# SIGNAL1.net
KiCad netlist of a schematic drawn in Altium Designer
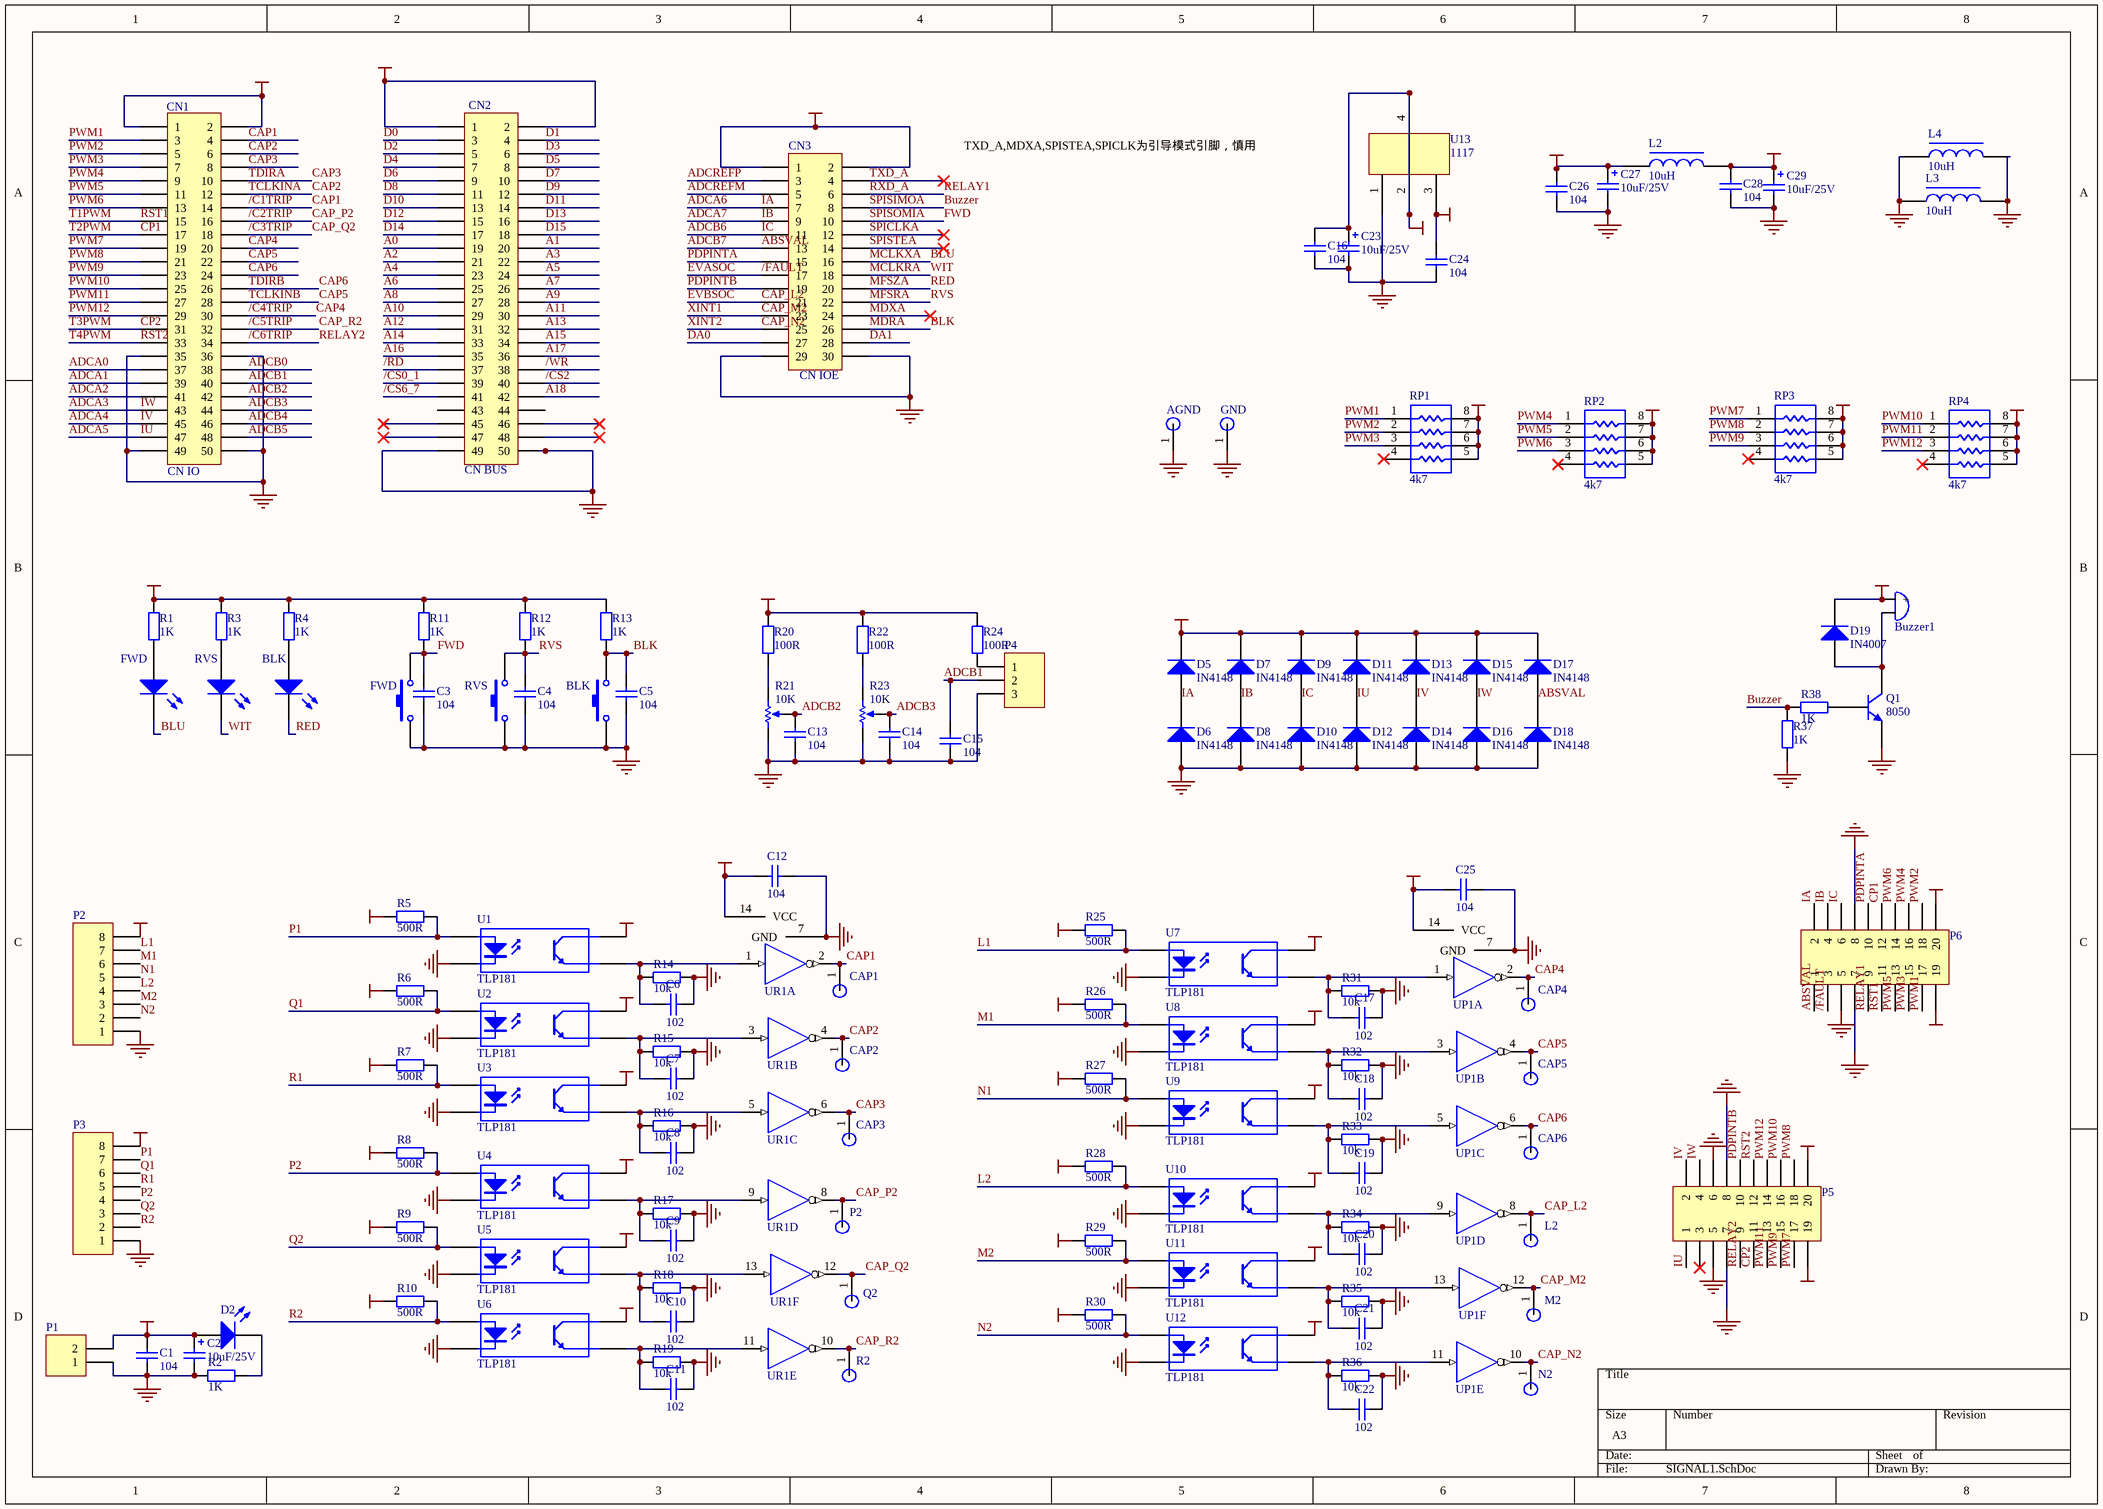
[diagram p0: SIGNAL1.SchDoc]

(export (version "E")
  (design (tool "Eeschema 10.0.6"))
  (components
    (comp (ref "Buzzer1")
      (value "BUZZER")
      (footprint "Buzzer")
      (description "蜂鸣器")
      (libsource (lib "Mylib") (part "BUZZER"))
    )
    (comp (ref "C1")
      (value "104")
      (footprint "C2012-0805")
      (description "普通电容")
      (libsource (lib "*") (part "Cap"))
    )
    (comp (ref "C2")
      (value "10uF/25V")
      (footprint "C_10UF/25V")
      (description "钽电解")
      (libsource (lib "Mylib") (part "Cap tan"))
    )
    (comp (ref "C3")
      (value "104")
      (footprint "C2012-0805")
      (description "普通电容")
      (libsource (lib "Mylib") (part "Cap"))
    )
    (comp (ref "C4")
      (value "104")
      (footprint "C2012-0805")
      (description "普通电容")
      (libsource (lib "Mylib") (part "Cap"))
    )
    (comp (ref "C5")
      (value "104")
      (footprint "C2012-0805")
      (description "普通电容")
      (libsource (lib "Mylib") (part "Cap"))
    )
    (comp (ref "C6")
      (value "102")
      (footprint "C2012-0805")
      (description "普通电容")
      (libsource (lib "*") (part "Cap"))
    )
    (comp (ref "C7")
      (value "102")
      (footprint "C2012-0805")
      (description "普通电容")
      (libsource (lib "*") (part "Cap"))
    )
    (comp (ref "C8")
      (value "102")
      (footprint "C2012-0805")
      (description "普通电容")
      (libsource (lib "*") (part "Cap"))
    )
    (comp (ref "C9")
      (value "102")
      (footprint "C2012-0805")
      (description "普通电容")
      (libsource (lib "*") (part "Cap"))
    )
    (comp (ref "C10")
      (value "102")
      (footprint "C2012-0805")
      (description "普通电容")
      (libsource (lib "*") (part "Cap"))
    )
    (comp (ref "C11")
      (value "102")
      (footprint "C2012-0805")
      (description "普通电容")
      (libsource (lib "*") (part "Cap"))
    )
    (comp (ref "C12")
      (value "104")
      (footprint "C2012-0805")
      (description "普通电容")
      (libsource (lib "*") (part "Cap"))
    )
    (comp (ref "C13")
      (value "104")
      (footprint "C2012-0805")
      (description "普通电容")
      (libsource (lib "Mylib") (part "Cap"))
    )
    (comp (ref "C14")
      (value "104")
      (footprint "C2012-0805")
      (description "普通电容")
      (libsource (lib "Mylib") (part "Cap"))
    )
    (comp (ref "C15")
      (value "104")
      (footprint "C2012-0805")
      (description "普通电容")
      (libsource (lib "Mylib") (part "Cap"))
    )
    (comp (ref "C16")
      (value "104")
      (footprint "C2012-0805")
      (description "普通电容")
      (libsource (lib "*") (part "Cap"))
    )
    (comp (ref "C17")
      (value "102")
      (footprint "C2012-0805")
      (description "普通电容")
      (libsource (lib "*") (part "Cap"))
    )
    (comp (ref "C18")
      (value "102")
      (footprint "C2012-0805")
      (description "普通电容")
      (libsource (lib "*") (part "Cap"))
    )
    (comp (ref "C19")
      (value "102")
      (footprint "C2012-0805")
      (description "普通电容")
      (libsource (lib "*") (part "Cap"))
    )
    (comp (ref "C20")
      (value "102")
      (footprint "C2012-0805")
      (description "普通电容")
      (libsource (lib "*") (part "Cap"))
    )
    (comp (ref "C21")
      (value "102")
      (footprint "C2012-0805")
      (description "普通电容")
      (libsource (lib "*") (part "Cap"))
    )
    (comp (ref "C22")
      (value "102")
      (footprint "C2012-0805")
      (description "普通电容")
      (libsource (lib "*") (part "Cap"))
    )
    (comp (ref "C23")
      (value "10uF/25V")
      (footprint "C_10UF/25V")
      (description "钽电解")
      (libsource (lib "Mylib") (part "Cap tan"))
    )
    (comp (ref "C24")
      (value "104")
      (footprint "C2012-0805")
      (description "普通电容")
      (libsource (lib "*") (part "Cap"))
    )
    (comp (ref "C25")
      (value "104")
      (footprint "C2012-0805")
      (description "普通电容")
      (libsource (lib "*") (part "Cap"))
    )
    (comp (ref "C26")
      (value "104")
      (footprint "C2012-0805")
      (description "普通电容")
      (libsource (lib "*") (part "Cap"))
    )
    (comp (ref "C27")
      (value "10uF/25V")
      (footprint "C_10UF/25V")
      (description "钽电解")
      (libsource (lib "Mylib") (part "Cap tan"))
    )
    (comp (ref "C28")
      (value "104")
      (footprint "C2012-0805")
      (description "普通电容")
      (libsource (lib "*") (part "Cap"))
    )
    (comp (ref "C29")
      (value "10uF/25V")
      (footprint "C_10UF/25V")
      (description "钽电解")
      (libsource (lib "Mylib") (part "Cap tan"))
    )
    (comp (ref "CN1")
      (value "CN IO")
      (footprint "HDR2X25")
      (description "Header, 25-Pin, Dual row")
      (fields (field (name "PUBLISHER") "Altium Limited"))
      (libsource (lib "Miscellaneous Connectors") (part "Header 25X2"))
    )
    (comp (ref "CN2")
      (value "CN BUS")
      (footprint "HDR2X25")
      (description "Header, 25-Pin, Dual row")
      (fields (field (name "PUBLISHER") "Altium Limited"))
      (libsource (lib "Miscellaneous Connectors") (part "Header 25X2"))
    )
    (comp (ref "CN3")
      (value "CN IOE")
      (footprint "HDR2X15")
      (description "Header, 15-Pin, Dual row")
      (fields (field (name "PUBLISHER") "Altium Limited"))
      (libsource (lib "Miscellaneous Connectors") (part "Header 15X2"))
    )
    (comp (ref "D1") (value "FWD") (footprint "LED-SMD") (libsource (lib "*") (part "LED")))
    (comp (ref "D2") (value "~") (footprint "LED-SMD") (libsource (lib "Mylib") (part "LED")))
    (comp (ref "D3") (value "RVS") (footprint "LED-SMD") (libsource (lib "*") (part "LED")))
    (comp (ref "D4") (value "BLK") (footprint "LED-SMD") (libsource (lib "*") (part "LED")))
    (comp (ref "D5")
      (value "IN4148")
      (footprint "IN4148")
      (description "开关二极管")
      (libsource (lib "Mylib") (part "Diode IN4148"))
    )
    (comp (ref "D6")
      (value "IN4148")
      (footprint "IN4148")
      (description "开关二极管")
      (libsource (lib "Mylib") (part "Diode IN4148"))
    )
    (comp (ref "D7")
      (value "IN4148")
      (footprint "IN4148")
      (description "开关二极管")
      (libsource (lib "Mylib") (part "Diode IN4148"))
    )
    (comp (ref "D8")
      (value "IN4148")
      (footprint "IN4148")
      (description "开关二极管")
      (libsource (lib "Mylib") (part "Diode IN4148"))
    )
    (comp (ref "D9")
      (value "IN4148")
      (footprint "IN4148")
      (description "开关二极管")
      (libsource (lib "Mylib") (part "Diode IN4148"))
    )
    (comp (ref "D10")
      (value "IN4148")
      (footprint "IN4148")
      (description "开关二极管")
      (libsource (lib "Mylib") (part "Diode IN4148"))
    )
    (comp (ref "D11")
      (value "IN4148")
      (footprint "IN4148")
      (description "开关二极管")
      (libsource (lib "Mylib") (part "Diode IN4148"))
    )
    (comp (ref "D12")
      (value "IN4148")
      (footprint "IN4148")
      (description "开关二极管")
      (libsource (lib "Mylib") (part "Diode IN4148"))
    )
    (comp (ref "D13")
      (value "IN4148")
      (footprint "IN4148")
      (description "开关二极管")
      (libsource (lib "Mylib") (part "Diode IN4148"))
    )
    (comp (ref "D14")
      (value "IN4148")
      (footprint "IN4148")
      (description "开关二极管")
      (libsource (lib "Mylib") (part "Diode IN4148"))
    )
    (comp (ref "D15")
      (value "IN4148")
      (footprint "IN4148")
      (description "开关二极管")
      (libsource (lib "Mylib") (part "Diode IN4148"))
    )
    (comp (ref "D16")
      (value "IN4148")
      (footprint "IN4148")
      (description "开关二极管")
      (libsource (lib "Mylib") (part "Diode IN4148"))
    )
    (comp (ref "D17")
      (value "IN4148")
      (footprint "IN4148")
      (description "开关二极管")
      (libsource (lib "Mylib") (part "Diode IN4148"))
    )
    (comp (ref "D18")
      (value "IN4148")
      (footprint "IN4148")
      (description "开关二极管")
      (libsource (lib "Mylib") (part "Diode IN4148"))
    )
    (comp (ref "D19")
      (value "IN4007")
      (footprint "DIODE4007")
      (description "普通整流二极管")
      (libsource (lib "Mylib") (part "Diode IN4007"))
    )
    (comp (ref "key1")
      (value "FWD")
      (footprint "KEY1")
      (description "按键")
      (libsource (lib "Mylib") (part "KEY"))
    )
    (comp (ref "key2")
      (value "RVS")
      (footprint "KEY1")
      (description "按键")
      (libsource (lib "Mylib") (part "KEY"))
    )
    (comp (ref "key3")
      (value "BLK")
      (footprint "KEY1")
      (description "按键")
      (libsource (lib "Mylib") (part "KEY"))
    )
    (comp (ref "L2") (value "10uH") (footprint "R2012-0805") (libsource (lib "*") (part "Inductor")))
    (comp (ref "L3") (value "10uH") (footprint "R2012-0805") (libsource (lib "*") (part "Inductor")))
    (comp (ref "L4") (value "10uH") (footprint "R2012-0805") (libsource (lib "*") (part "Inductor")))
    (comp (ref "P1")
      (value "Header 2")
      (footprint "HDR1X2")
      (description "Header, 2-Pin")
      (fields (field (name "PUBLISHER") "Altium Limited"))
      (libsource (lib "Miscellaneous Connectors") (part "Header 2"))
    )
    (comp (ref "P2")
      (value "Header 8")
      (footprint "HDR1X8")
      (description "Header, 8-Pin")
      (fields (field (name "PUBLISHER") "Altium Limited"))
      (libsource (lib "Miscellaneous Connectors") (part "Header 8"))
    )
    (comp (ref "P3")
      (value "Header 8")
      (footprint "HDR1X8")
      (description "Header, 8-Pin")
      (fields (field (name "PUBLISHER") "Altium Limited"))
      (libsource (lib "Miscellaneous Connectors") (part "Header 8"))
    )
    (comp (ref "P4")
      (value "Header 3")
      (footprint "HDR1X3")
      (description "Header, 3-Pin")
      (fields (field (name "PUBLISHER") "Altium Limited"))
      (libsource (lib "Miscellaneous Connectors") (part "Header 3"))
    )
    (comp (ref "P5")
      (value "Header 10X2")
      (footprint "HDR2X10")
      (description "Header, 10-Pin, Dual row")
      (fields (field (name "PUBLISHER") "Altium Limited"))
      (libsource (lib "Miscellaneous Connectors") (part "Header 10X2"))
    )
    (comp (ref "P6")
      (value "Header 10X2")
      (footprint "HDR2X10")
      (description "Header, 10-Pin, Dual row")
      (fields (field (name "PUBLISHER") "Altium Limited"))
      (libsource (lib "Miscellaneous Connectors") (part "Header 10X2"))
    )
    (comp (ref "Q1") (value "8050") (footprint "NPN8050") (libsource (lib "Mylib") (part "NPN8050")))
    (comp (ref "R1") (value "1K") (footprint "R2012-0805") (libsource (lib "") (part "Res_2")))
    (comp (ref "R2") (value "1K") (footprint "R2012-0805") (libsource (lib "*") (part "Res")))
    (comp (ref "R3") (value "1K") (footprint "R2012-0805") (libsource (lib "") (part "Res_2")))
    (comp (ref "R4") (value "1K") (footprint "R2012-0805") (libsource (lib "") (part "Res_2")))
    (comp (ref "R5") (value "500R") (footprint "R2012-0805") (libsource (lib "Mylib") (part "Res")))
    (comp (ref "R6") (value "500R") (footprint "R2012-0805") (libsource (lib "Mylib") (part "Res")))
    (comp (ref "R7") (value "500R") (footprint "R2012-0805") (libsource (lib "Mylib") (part "Res")))
    (comp (ref "R8") (value "500R") (footprint "R2012-0805") (libsource (lib "Mylib") (part "Res")))
    (comp (ref "R9") (value "500R") (footprint "R2012-0805") (libsource (lib "Mylib") (part "Res")))
    (comp (ref "R10") (value "500R") (footprint "R2012-0805") (libsource (lib "Mylib") (part "Res")))
    (comp (ref "R11") (value "1K") (footprint "R2012-0805") (libsource (lib "") (part "Res_2")))
    (comp (ref "R12") (value "1K") (footprint "R2012-0805") (libsource (lib "") (part "Res_2")))
    (comp (ref "R13") (value "1K") (footprint "R2012-0805") (libsource (lib "") (part "Res_2")))
    (comp (ref "R14") (value "10k") (footprint "R2012-0805") (libsource (lib "Mylib") (part "Res")))
    (comp (ref "R15") (value "10k") (footprint "R2012-0805") (libsource (lib "Mylib") (part "Res")))
    (comp (ref "R16") (value "10k") (footprint "R2012-0805") (libsource (lib "Mylib") (part "Res")))
    (comp (ref "R17") (value "10k") (footprint "R2012-0805") (libsource (lib "Mylib") (part "Res")))
    (comp (ref "R18") (value "10k") (footprint "R2012-0805") (libsource (lib "Mylib") (part "Res")))
    (comp (ref "R19") (value "10k") (footprint "R2012-0805") (libsource (lib "Mylib") (part "Res")))
    (comp (ref "R20") (value "100R") (footprint "R2012-0805") (libsource (lib "") (part "Res_2")))
    (comp (ref "R21")
      (value "10K")
      (footprint "Res3296")
      (description "微调电位器")
      (libsource (lib "Mylib") (part "Res3296"))
    )
    (comp (ref "R22") (value "100R") (footprint "R2012-0805") (libsource (lib "") (part "Res_2")))
    (comp (ref "R23")
      (value "10K")
      (footprint "Res3296")
      (description "微调电位器")
      (libsource (lib "Mylib") (part "Res3296"))
    )
    (comp (ref "R24") (value "100R") (footprint "R2012-0805") (libsource (lib "") (part "Res_2")))
    (comp (ref "R25") (value "500R") (footprint "R2012-0805") (libsource (lib "Mylib") (part "Res")))
    (comp (ref "R26") (value "500R") (footprint "R2012-0805") (libsource (lib "Mylib") (part "Res")))
    (comp (ref "R27") (value "500R") (footprint "R2012-0805") (libsource (lib "Mylib") (part "Res")))
    (comp (ref "R28") (value "500R") (footprint "R2012-0805") (libsource (lib "Mylib") (part "Res")))
    (comp (ref "R29") (value "500R") (footprint "R2012-0805") (libsource (lib "Mylib") (part "Res")))
    (comp (ref "R30") (value "500R") (footprint "R2012-0805") (libsource (lib "Mylib") (part "Res")))
    (comp (ref "R31") (value "10k") (footprint "R2012-0805") (libsource (lib "Mylib") (part "Res")))
    (comp (ref "R32") (value "10k") (footprint "R2012-0805") (libsource (lib "Mylib") (part "Res")))
    (comp (ref "R33") (value "10k") (footprint "R2012-0805") (libsource (lib "Mylib") (part "Res")))
    (comp (ref "R34") (value "10k") (footprint "R2012-0805") (libsource (lib "Mylib") (part "Res")))
    (comp (ref "R35") (value "10k") (footprint "R2012-0805") (libsource (lib "Mylib") (part "Res")))
    (comp (ref "R36") (value "10k") (footprint "R2012-0805") (libsource (lib "Mylib") (part "Res")))
    (comp (ref "R37") (value "1K") (footprint "R2012-0805") (libsource (lib "") (part "Res_3")))
    (comp (ref "R38") (value "1K") (footprint "R2012-0805") (libsource (lib "") (part "Res_1")))
    (comp (ref "RP1") (value "4k7") (footprint "Res_Pack4") (libsource (lib "Mylib") (part "Res_Pack4")))
    (comp (ref "RP2") (value "4k7") (footprint "Res_Pack4") (libsource (lib "Mylib") (part "Res_Pack4")))
    (comp (ref "RP3") (value "4k7") (footprint "Res_Pack4") (libsource (lib "Mylib") (part "Res_Pack4")))
    (comp (ref "RP4") (value "4k7") (footprint "Res_Pack4") (libsource (lib "Mylib") (part "Res_Pack4")))
    (comp (ref "T1")
      (value "CAP1")
      (footprint "PIN1")
      (description "测试脚")
      (libsource (lib "Mylib") (part "TP"))
    )
    (comp (ref "T2")
      (value "CAP2")
      (footprint "PIN1")
      (description "测试脚")
      (libsource (lib "Mylib") (part "TP"))
    )
    (comp (ref "T3")
      (value "P2")
      (footprint "PIN1")
      (description "测试脚")
      (libsource (lib "Mylib") (part "TP"))
    )
    (comp (ref "T4")
      (value "CAP3")
      (footprint "PIN1")
      (description "测试脚")
      (libsource (lib "Mylib") (part "TP"))
    )
    (comp (ref "T5")
      (value "R2")
      (footprint "PIN1")
      (description "测试脚")
      (libsource (lib "Mylib") (part "TP"))
    )
    (comp (ref "T6")
      (value "Q2")
      (footprint "PIN1")
      (description "测试脚")
      (libsource (lib "Mylib") (part "TP"))
    )
    (comp (ref "T7")
      (value "AGND")
      (footprint "PIN1")
      (description "测试脚")
      (libsource (lib "Mylib") (part "TP"))
    )
    (comp (ref "T8")
      (value "GND")
      (footprint "PIN1")
      (description "测试脚")
      (libsource (lib "Mylib") (part "TP"))
    )
    (comp (ref "T9")
      (value "CAP4")
      (footprint "PIN1")
      (description "测试脚")
      (libsource (lib "Mylib") (part "TP"))
    )
    (comp (ref "T10")
      (value "CAP5")
      (footprint "PIN1")
      (description "测试脚")
      (libsource (lib "Mylib") (part "TP"))
    )
    (comp (ref "T11")
      (value "CAP6")
      (footprint "PIN1")
      (description "测试脚")
      (libsource (lib "Mylib") (part "TP"))
    )
    (comp (ref "T12")
      (value "L2")
      (footprint "PIN1")
      (description "测试脚")
      (libsource (lib "Mylib") (part "TP"))
    )
    (comp (ref "T13")
      (value "N2")
      (footprint "PIN1")
      (description "测试脚")
      (libsource (lib "Mylib") (part "TP"))
    )
    (comp (ref "T14")
      (value "M2")
      (footprint "PIN1")
      (description "测试脚")
      (libsource (lib "Mylib") (part "TP"))
    )
    (comp (ref "U1") (value "TLP181") (footprint "TLP181") (libsource (lib "Mylib") (part "TLP181")))
    (comp (ref "U2") (value "TLP181") (footprint "TLP181") (libsource (lib "Mylib") (part "TLP181")))
    (comp (ref "U3") (value "TLP181") (footprint "TLP181") (libsource (lib "Mylib") (part "TLP181")))
    (comp (ref "U4") (value "TLP181") (footprint "TLP181") (libsource (lib "Mylib") (part "TLP181")))
    (comp (ref "U5") (value "TLP181") (footprint "TLP181") (libsource (lib "Mylib") (part "TLP181")))
    (comp (ref "U6") (value "TLP181") (footprint "TLP181") (libsource (lib "Mylib") (part "TLP181")))
    (comp (ref "U7") (value "TLP181") (footprint "TLP181") (libsource (lib "Mylib") (part "TLP181")))
    (comp (ref "U8") (value "TLP181") (footprint "TLP181") (libsource (lib "Mylib") (part "TLP181")))
    (comp (ref "U9") (value "TLP181") (footprint "TLP181") (libsource (lib "Mylib") (part "TLP181")))
    (comp (ref "U10") (value "TLP181") (footprint "TLP181") (libsource (lib "Mylib") (part "TLP181")))
    (comp (ref "U11") (value "TLP181") (footprint "TLP181") (libsource (lib "Mylib") (part "TLP181")))
    (comp (ref "U12") (value "TLP181") (footprint "TLP181") (libsource (lib "Mylib") (part "TLP181")))
    (comp (ref "U13") (value "1117") (footprint "1117-3.3V") (libsource (lib "*") (part "1117")))
    (comp (ref "UP1")
      (value "74HC14")
      (footprint "74HC14")
      (description "六路，施密特触发反相器")
      (libsource (lib "*") (part "74HC14"))
    )
    (comp (ref "UR1")
      (value "74HC14")
      (footprint "74HC14")
      (description "六路，施密特触发反相器")
      (libsource (lib "*") (part "74HC14"))
    )
  )
  (nets
    (net (code "1") (name "+5V") (class "Default")
      (node (ref "Buzzer1") (pin "1") (pinfunction "+_1") (pintype "passive"))
      (node (ref "C26") (pin "2") (pinfunction "2_2") (pintype "passive"))
      (node (ref "C27") (pin "1") (pinfunction "1_1") (pintype "passive"))
      (node (ref "CN1") (pin "1") (pinfunction "1_1") (pintype "passive"))
      (node (ref "CN1") (pin "2") (pinfunction "2_2") (pintype "passive"))
      (node (ref "CN2") (pin "1") (pinfunction "1_1") (pintype "passive"))
      (node (ref "CN2") (pin "2") (pinfunction "2_2") (pintype "passive"))
      (node (ref "CN3") (pin "1") (pinfunction "1_1") (pintype "passive"))
      (node (ref "CN3") (pin "2") (pinfunction "2_2") (pintype "passive"))
      (node (ref "D19") (pin "2") (pinfunction "K_2") (pintype "passive"))
      (node (ref "L2") (pin "1") (pinfunction "1_1") (pintype "passive"))
      (node (ref "P5") (pin "19") (pinfunction "19_19") (pintype "passive"))
      (node (ref "P5") (pin "20") (pinfunction "20_20") (pintype "passive"))
      (node (ref "P6") (pin "19") (pinfunction "19_19") (pintype "passive"))
      (node (ref "P6") (pin "20") (pinfunction "20_20") (pintype "passive"))
    )
    (net (code "2") (name "+5V_HALL") (class "Default")
      (node (ref "C1") (pin "2") (pinfunction "2_2") (pintype "passive"))
      (node (ref "C2") (pin "1") (pinfunction "1_1") (pintype "passive"))
      (node (ref "D2") (pin "1") (pinfunction "A_1") (pintype "passive"))
      (node (ref "P1") (pin "2") (pinfunction "2_2") (pintype "passive"))
      (node (ref "P2") (pin "8") (pinfunction "8_8") (pintype "passive"))
      (node (ref "P3") (pin "8") (pinfunction "8_8") (pintype "passive"))
      (node (ref "R10") (pin "1") (pinfunction "1_1") (pintype "passive"))
      (node (ref "R25") (pin "1") (pinfunction "1_1") (pintype "passive"))
      (node (ref "R26") (pin "1") (pinfunction "1_1") (pintype "passive"))
      (node (ref "R27") (pin "1") (pinfunction "1_1") (pintype "passive"))
      (node (ref "R28") (pin "1") (pinfunction "1_1") (pintype "passive"))
      (node (ref "R29") (pin "1") (pinfunction "1_1") (pintype "passive"))
      (node (ref "R30") (pin "1") (pinfunction "1_1") (pintype "passive"))
      (node (ref "R5") (pin "1") (pinfunction "1_1") (pintype "passive"))
      (node (ref "R6") (pin "1") (pinfunction "1_1") (pintype "passive"))
      (node (ref "R7") (pin "1") (pinfunction "1_1") (pintype "passive"))
      (node (ref "R8") (pin "1") (pinfunction "1_1") (pintype "passive"))
      (node (ref "R9") (pin "1") (pinfunction "1_1") (pintype "passive"))
    )
    (net (code "3") (name "/A0") (class "Default")
      (node (ref "CN2") (pin "19") (pinfunction "19_19") (pintype "passive"))
    )
    (net (code "4") (name "/A1") (class "Default")
      (node (ref "CN2") (pin "20") (pinfunction "20_20") (pintype "passive"))
    )
    (net (code "5") (name "/A2") (class "Default")
      (node (ref "CN2") (pin "21") (pinfunction "21_21") (pintype "passive"))
    )
    (net (code "6") (name "/A3") (class "Default")
      (node (ref "CN2") (pin "22") (pinfunction "22_22") (pintype "passive"))
    )
    (net (code "7") (name "/A4") (class "Default")
      (node (ref "CN2") (pin "23") (pinfunction "23_23") (pintype "passive"))
    )
    (net (code "8") (name "/A5") (class "Default")
      (node (ref "CN2") (pin "24") (pinfunction "24_24") (pintype "passive"))
    )
    (net (code "9") (name "/A6") (class "Default")
      (node (ref "CN2") (pin "25") (pinfunction "25_25") (pintype "passive"))
    )
    (net (code "10") (name "/A7") (class "Default")
      (node (ref "CN2") (pin "26") (pinfunction "26_26") (pintype "passive"))
    )
    (net (code "11") (name "/A8") (class "Default")
      (node (ref "CN2") (pin "27") (pinfunction "27_27") (pintype "passive"))
    )
    (net (code "12") (name "/A9") (class "Default")
      (node (ref "CN2") (pin "28") (pinfunction "28_28") (pintype "passive"))
    )
    (net (code "13") (name "/A10") (class "Default")
      (node (ref "CN2") (pin "29") (pinfunction "29_29") (pintype "passive"))
    )
    (net (code "14") (name "/A11") (class "Default")
      (node (ref "CN2") (pin "30") (pinfunction "30_30") (pintype "passive"))
    )
    (net (code "15") (name "/A12") (class "Default")
      (node (ref "CN2") (pin "31") (pinfunction "31_31") (pintype "passive"))
    )
    (net (code "16") (name "/A13") (class "Default")
      (node (ref "CN2") (pin "32") (pinfunction "32_32") (pintype "passive"))
    )
    (net (code "17") (name "/A14") (class "Default")
      (node (ref "CN2") (pin "33") (pinfunction "33_33") (pintype "passive"))
    )
    (net (code "18") (name "/A15") (class "Default")
      (node (ref "CN2") (pin "34") (pinfunction "34_34") (pintype "passive"))
    )
    (net (code "19") (name "/A16") (class "Default")
      (node (ref "CN2") (pin "35") (pinfunction "35_35") (pintype "passive"))
    )
    (net (code "20") (name "/A17") (class "Default")
      (node (ref "CN2") (pin "36") (pinfunction "36_36") (pintype "passive"))
    )
    (net (code "21") (name "/A18") (class "Default")
      (node (ref "CN2") (pin "42") (pinfunction "42_42") (pintype "passive"))
    )
    (net (code "22") (name "/ABSVAL") (class "Default")
      (node (ref "CN3") (pin "13") (pinfunction "13_13") (pintype "passive"))
      (node (ref "D17") (pin "1") (pinfunction "A_1") (pintype "passive"))
      (node (ref "D18") (pin "2") (pinfunction "K_2") (pintype "passive"))
      (node (ref "P6") (pin "1") (pinfunction "1_1") (pintype "passive"))
    )
    (net (code "23") (name "/ADCA0") (class "Default")
      (node (ref "CN1") (pin "37") (pinfunction "37_37") (pintype "passive"))
    )
    (net (code "24") (name "/ADCA1") (class "Default")
      (node (ref "CN1") (pin "39") (pinfunction "39_39") (pintype "passive"))
    )
    (net (code "25") (name "/ADCA2") (class "Default")
      (node (ref "CN1") (pin "41") (pinfunction "41_41") (pintype "passive"))
    )
    (net (code "26") (name "/ADCA3") (class "Default")
      (node (ref "CN1") (pin "43") (pinfunction "43_43") (pintype "passive"))
      (node (ref "D15") (pin "1") (pinfunction "A_1") (pintype "passive"))
      (node (ref "D16") (pin "2") (pinfunction "K_2") (pintype "passive"))
      (node (ref "P5") (pin "4") (pinfunction "4_4") (pintype "passive"))
    )
    (net (code "27") (name "/ADCA4") (class "Default")
      (node (ref "CN1") (pin "45") (pinfunction "45_45") (pintype "passive"))
      (node (ref "D13") (pin "1") (pinfunction "A_1") (pintype "passive"))
      (node (ref "D14") (pin "2") (pinfunction "K_2") (pintype "passive"))
      (node (ref "P5") (pin "2") (pinfunction "2_2") (pintype "passive"))
    )
    (net (code "28") (name "/ADCA5") (class "Default")
      (node (ref "CN1") (pin "47") (pinfunction "47_47") (pintype "passive"))
      (node (ref "D11") (pin "1") (pinfunction "A_1") (pintype "passive"))
      (node (ref "D12") (pin "2") (pinfunction "K_2") (pintype "passive"))
      (node (ref "P5") (pin "1") (pinfunction "1_1") (pintype "passive"))
    )
    (net (code "29") (name "/ADCA6") (class "Default")
      (node (ref "CN3") (pin "7") (pinfunction "7_7") (pintype "passive"))
      (node (ref "D5") (pin "1") (pinfunction "A_1") (pintype "passive"))
      (node (ref "D6") (pin "2") (pinfunction "K_2") (pintype "passive"))
      (node (ref "P6") (pin "2") (pinfunction "2_2") (pintype "passive"))
    )
    (net (code "30") (name "/ADCA7") (class "Default")
      (node (ref "CN3") (pin "9") (pinfunction "9_9") (pintype "passive"))
      (node (ref "D7") (pin "1") (pinfunction "A_1") (pintype "passive"))
      (node (ref "D8") (pin "2") (pinfunction "K_2") (pintype "passive"))
      (node (ref "P6") (pin "4") (pinfunction "4_4") (pintype "passive"))
    )
    (net (code "31") (name "/ADCB0") (class "Default")
      (node (ref "CN1") (pin "38") (pinfunction "38_38") (pintype "passive"))
    )
    (net (code "32") (name "/ADCB1") (class "Default")
      (node (ref "C15") (pin "2") (pinfunction "2_2") (pintype "passive"))
      (node (ref "CN1") (pin "40") (pinfunction "40_40") (pintype "passive"))
      (node (ref "P4") (pin "2") (pinfunction "2_2") (pintype "passive"))
    )
    (net (code "33") (name "/ADCB2") (class "Default")
      (node (ref "C13") (pin "2") (pinfunction "2_2") (pintype "passive"))
      (node (ref "CN1") (pin "42") (pinfunction "42_42") (pintype "passive"))
      (node (ref "R21") (pin "2") (pinfunction "TAP_2") (pintype "passive"))
    )
    (net (code "34") (name "/ADCB3") (class "Default")
      (node (ref "C14") (pin "2") (pinfunction "2_2") (pintype "passive"))
      (node (ref "CN1") (pin "44") (pinfunction "44_44") (pintype "passive"))
      (node (ref "R23") (pin "2") (pinfunction "TAP_2") (pintype "passive"))
    )
    (net (code "35") (name "/ADCB4") (class "Default")
      (node (ref "CN1") (pin "46") (pinfunction "46_46") (pintype "passive"))
    )
    (net (code "36") (name "/ADCB5") (class "Default")
      (node (ref "CN1") (pin "48") (pinfunction "48_48") (pintype "passive"))
    )
    (net (code "37") (name "/ADCB6") (class "Default")
      (node (ref "CN3") (pin "11") (pinfunction "11_11") (pintype "passive"))
      (node (ref "D10") (pin "2") (pinfunction "K_2") (pintype "passive"))
      (node (ref "D9") (pin "1") (pinfunction "A_1") (pintype "passive"))
      (node (ref "P6") (pin "6") (pinfunction "6_6") (pintype "passive"))
    )
    (net (code "38") (name "/ADCREFM") (class "Default")
      (node (ref "CN3") (pin "5") (pinfunction "5_5") (pintype "passive"))
    )
    (net (code "39") (name "/ADCREFP") (class "Default")
      (node (ref "CN3") (pin "3") (pinfunction "3_3") (pintype "passive"))
    )
    (net (code "40") (name "/BLK") (class "Default")
      (node (ref "C5") (pin "2") (pinfunction "2_2") (pintype "passive"))
      (node (ref "CN3") (pin "26") (pinfunction "26_26") (pintype "passive"))
      (node (ref "R13") (pin "1") (pinfunction "1_1") (pintype "passive"))
      (node (ref "key3") (pin "3") (pinfunction "3_3") (pintype "passive"))
    )
    (net (code "41") (name "/BLU") (class "Default")
      (node (ref "CN3") (pin "16") (pinfunction "16_16") (pintype "passive"))
      (node (ref "D1") (pin "2") (pinfunction "K_2") (pintype "passive"))
    )
    (net (code "42") (name "/Buzzer") (class "Default")
      (node (ref "CN3") (pin "8") (pinfunction "8_8") (pintype "passive"))
      (node (ref "R37") (pin "1") (pinfunction "1_1") (pintype "passive"))
      (node (ref "R38") (pin "2") (pinfunction "2_2") (pintype "passive"))
    )
    (net (code "43") (name "/CAP1") (class "Default")
      (node (ref "CN1") (pin "14") (pinfunction "14_14") (pintype "passive"))
      (node (ref "CN1") (pin "4") (pinfunction "4_4") (pintype "passive"))
      (node (ref "T1") (pin "1") (pinfunction "A_1") (pintype "passive"))
      (node (ref "UR1") (pin "2") (pinfunction "Y_2") (pintype "output"))
    )
    (net (code "44") (name "/CAP2") (class "Default")
      (node (ref "CN1") (pin "12") (pinfunction "12_12") (pintype "passive"))
      (node (ref "CN1") (pin "6") (pinfunction "6_6") (pintype "passive"))
      (node (ref "T2") (pin "1") (pinfunction "A_1") (pintype "passive"))
      (node (ref "UR1") (pin "4") (pinfunction "Y_4") (pintype "output"))
    )
    (net (code "45") (name "/CAP3") (class "Default")
      (node (ref "CN1") (pin "10") (pinfunction "10_10") (pintype "passive"))
      (node (ref "CN1") (pin "8") (pinfunction "8_8") (pintype "passive"))
      (node (ref "T4") (pin "1") (pinfunction "A_1") (pintype "passive"))
      (node (ref "UR1") (pin "6") (pinfunction "Y_6") (pintype "output"))
    )
    (net (code "46") (name "/CAP4") (class "Default")
      (node (ref "CN1") (pin "20") (pinfunction "20_20") (pintype "passive"))
      (node (ref "CN1") (pin "30") (pinfunction "30_30") (pintype "passive"))
      (node (ref "T9") (pin "1") (pinfunction "A_1") (pintype "passive"))
      (node (ref "UP1") (pin "2") (pinfunction "Y_2") (pintype "output"))
    )
    (net (code "47") (name "/CAP5") (class "Default")
      (node (ref "CN1") (pin "22") (pinfunction "22_22") (pintype "passive"))
      (node (ref "CN1") (pin "28") (pinfunction "28_28") (pintype "passive"))
      (node (ref "T10") (pin "1") (pinfunction "A_1") (pintype "passive"))
      (node (ref "UP1") (pin "4") (pinfunction "Y_4") (pintype "output"))
    )
    (net (code "48") (name "/CAP6") (class "Default")
      (node (ref "CN1") (pin "24") (pinfunction "24_24") (pintype "passive"))
      (node (ref "CN1") (pin "26") (pinfunction "26_26") (pintype "passive"))
      (node (ref "T11") (pin "1") (pinfunction "A_1") (pintype "passive"))
      (node (ref "UP1") (pin "6") (pinfunction "Y_6") (pintype "output"))
    )
    (net (code "49") (name "/CAP_L2") (class "Default")
      (node (ref "CN3") (pin "21") (pinfunction "21_21") (pintype "passive"))
      (node (ref "T12") (pin "1") (pinfunction "A_1") (pintype "passive"))
      (node (ref "UP1") (pin "8") (pinfunction "Y_8") (pintype "output"))
    )
    (net (code "50") (name "/CAP_M2") (class "Default")
      (node (ref "CN3") (pin "23") (pinfunction "23_23") (pintype "passive"))
      (node (ref "T14") (pin "1") (pinfunction "A_1") (pintype "passive"))
      (node (ref "UP1") (pin "12") (pinfunction "Y_12") (pintype "output"))
    )
    (net (code "51") (name "/CAP_N2") (class "Default")
      (node (ref "CN3") (pin "25") (pinfunction "25_25") (pintype "passive"))
      (node (ref "T13") (pin "1") (pinfunction "A_1") (pintype "passive"))
      (node (ref "UP1") (pin "10") (pinfunction "Y_10") (pintype "output"))
    )
    (net (code "52") (name "/CAP_P2") (class "Default")
      (node (ref "CN1") (pin "16") (pinfunction "16_16") (pintype "passive"))
      (node (ref "T3") (pin "1") (pinfunction "A_1") (pintype "passive"))
      (node (ref "UR1") (pin "8") (pinfunction "Y_8") (pintype "output"))
    )
    (net (code "53") (name "/CAP_Q2") (class "Default")
      (node (ref "CN1") (pin "18") (pinfunction "18_18") (pintype "passive"))
      (node (ref "T6") (pin "1") (pinfunction "A_1") (pintype "passive"))
      (node (ref "UR1") (pin "12") (pinfunction "Y_12") (pintype "output"))
    )
    (net (code "54") (name "/CAP_R2") (class "Default")
      (node (ref "CN1") (pin "32") (pinfunction "32_32") (pintype "passive"))
      (node (ref "T5") (pin "1") (pinfunction "A_1") (pintype "passive"))
      (node (ref "UR1") (pin "10") (pinfunction "Y_10") (pintype "output"))
    )
    (net (code "55") (name "/CP1") (class "Default")
      (node (ref "CN1") (pin "17") (pinfunction "17_17") (pintype "passive"))
      (node (ref "P6") (pin "12") (pinfunction "12_12") (pintype "passive"))
    )
    (net (code "56") (name "/CP2") (class "Default")
      (node (ref "CN1") (pin "31") (pinfunction "31_31") (pintype "passive"))
      (node (ref "P5") (pin "11") (pinfunction "11_11") (pintype "passive"))
    )
    (net (code "57") (name "/D0") (class "Default")
      (node (ref "CN2") (pin "3") (pinfunction "3_3") (pintype "passive"))
    )
    (net (code "58") (name "/D1") (class "Default")
      (node (ref "CN2") (pin "4") (pinfunction "4_4") (pintype "passive"))
    )
    (net (code "59") (name "/D2") (class "Default")
      (node (ref "CN2") (pin "5") (pinfunction "5_5") (pintype "passive"))
    )
    (net (code "60") (name "/D3") (class "Default")
      (node (ref "CN2") (pin "6") (pinfunction "6_6") (pintype "passive"))
    )
    (net (code "61") (name "/D4") (class "Default")
      (node (ref "CN2") (pin "7") (pinfunction "7_7") (pintype "passive"))
    )
    (net (code "62") (name "/D5") (class "Default")
      (node (ref "CN2") (pin "8") (pinfunction "8_8") (pintype "passive"))
    )
    (net (code "63") (name "/D6") (class "Default")
      (node (ref "CN2") (pin "9") (pinfunction "9_9") (pintype "passive"))
    )
    (net (code "64") (name "/D7") (class "Default")
      (node (ref "CN2") (pin "10") (pinfunction "10_10") (pintype "passive"))
    )
    (net (code "65") (name "/D8") (class "Default")
      (node (ref "CN2") (pin "11") (pinfunction "11_11") (pintype "passive"))
    )
    (net (code "66") (name "/D9") (class "Default")
      (node (ref "CN2") (pin "12") (pinfunction "12_12") (pintype "passive"))
    )
    (net (code "67") (name "/D10") (class "Default")
      (node (ref "CN2") (pin "13") (pinfunction "13_13") (pintype "passive"))
    )
    (net (code "68") (name "/D11") (class "Default")
      (node (ref "CN2") (pin "14") (pinfunction "14_14") (pintype "passive"))
    )
    (net (code "69") (name "/D12") (class "Default")
      (node (ref "CN2") (pin "15") (pinfunction "15_15") (pintype "passive"))
    )
    (net (code "70") (name "/D13") (class "Default")
      (node (ref "CN2") (pin "16") (pinfunction "16_16") (pintype "passive"))
    )
    (net (code "71") (name "/D14") (class "Default")
      (node (ref "CN2") (pin "17") (pinfunction "17_17") (pintype "passive"))
    )
    (net (code "72") (name "/D15") (class "Default")
      (node (ref "CN2") (pin "18") (pinfunction "18_18") (pintype "passive"))
    )
    (net (code "73") (name "/DA0") (class "Default")
      (node (ref "CN3") (pin "27") (pinfunction "27_27") (pintype "passive"))
    )
    (net (code "74") (name "/DA1") (class "Default")
      (node (ref "CN3") (pin "28") (pinfunction "28_28") (pintype "passive"))
    )
    (net (code "75") (name "/EVASOC") (class "Default")
      (node (ref "CN3") (pin "17") (pinfunction "17_17") (pintype "passive"))
      (node (ref "P6") (pin "3") (pinfunction "3_3") (pintype "passive"))
    )
    (net (code "76") (name "/FWD") (class "Default")
      (node (ref "C3") (pin "2") (pinfunction "2_2") (pintype "passive"))
      (node (ref "CN3") (pin "10") (pinfunction "10_10") (pintype "passive"))
      (node (ref "R11") (pin "1") (pinfunction "1_1") (pintype "passive"))
      (node (ref "key1") (pin "3") (pinfunction "3_3") (pintype "passive"))
    )
    (net (code "77") (name "/L1") (class "Default")
      (node (ref "P2") (pin "7") (pinfunction "7_7") (pintype "passive"))
      (node (ref "R25") (pin "2") (pinfunction "2_2") (pintype "passive"))
      (node (ref "U7") (pin "1") (pinfunction "A_1") (pintype "passive"))
    )
    (net (code "78") (name "/L2") (class "Default")
      (node (ref "P2") (pin "4") (pinfunction "4_4") (pintype "passive"))
      (node (ref "R28") (pin "2") (pinfunction "2_2") (pintype "passive"))
      (node (ref "U10") (pin "1") (pinfunction "A_1") (pintype "passive"))
    )
    (net (code "79") (name "/M1") (class "Default")
      (node (ref "P2") (pin "6") (pinfunction "6_6") (pintype "passive"))
      (node (ref "R26") (pin "2") (pinfunction "2_2") (pintype "passive"))
      (node (ref "U8") (pin "1") (pinfunction "A_1") (pintype "passive"))
    )
    (net (code "80") (name "/M2") (class "Default")
      (node (ref "P2") (pin "3") (pinfunction "3_3") (pintype "passive"))
      (node (ref "R29") (pin "2") (pinfunction "2_2") (pintype "passive"))
      (node (ref "U11") (pin "1") (pinfunction "A_1") (pintype "passive"))
    )
    (net (code "81") (name "/MCLKRA") (class "Default")
      (node (ref "CN3") (pin "18") (pinfunction "18_18") (pintype "passive"))
      (node (ref "D3") (pin "2") (pinfunction "K_2") (pintype "passive"))
    )
    (net (code "82") (name "/MDXA") (class "Default")
      (node (ref "CN3") (pin "24") (pinfunction "24_24") (pintype "passive+no_connect"))
    )
    (net (code "83") (name "/MFSRA") (class "Default")
      (node (ref "C4") (pin "2") (pinfunction "2_2") (pintype "passive"))
      (node (ref "CN3") (pin "22") (pinfunction "22_22") (pintype "passive"))
      (node (ref "R12") (pin "1") (pinfunction "1_1") (pintype "passive"))
      (node (ref "key2") (pin "3") (pinfunction "3_3") (pintype "passive"))
    )
    (net (code "84") (name "/MFSZA") (class "Default")
      (node (ref "CN3") (pin "20") (pinfunction "20_20") (pintype "passive"))
      (node (ref "D4") (pin "2") (pinfunction "K_2") (pintype "passive"))
    )
    (net (code "85") (name "/N1") (class "Default")
      (node (ref "P2") (pin "5") (pinfunction "5_5") (pintype "passive"))
      (node (ref "R27") (pin "2") (pinfunction "2_2") (pintype "passive"))
      (node (ref "U9") (pin "1") (pinfunction "A_1") (pintype "passive"))
    )
    (net (code "86") (name "/N2") (class "Default")
      (node (ref "P2") (pin "2") (pinfunction "2_2") (pintype "passive"))
      (node (ref "R30") (pin "2") (pinfunction "2_2") (pintype "passive"))
      (node (ref "U12") (pin "1") (pinfunction "A_1") (pintype "passive"))
    )
    (net (code "87") (name "/P1") (class "Default")
      (node (ref "P3") (pin "7") (pinfunction "7_7") (pintype "passive"))
      (node (ref "R5") (pin "2") (pinfunction "2_2") (pintype "passive"))
      (node (ref "U1") (pin "1") (pinfunction "A_1") (pintype "passive"))
    )
    (net (code "88") (name "/P2") (class "Default")
      (node (ref "P3") (pin "4") (pinfunction "4_4") (pintype "passive"))
      (node (ref "R8") (pin "2") (pinfunction "2_2") (pintype "passive"))
      (node (ref "U4") (pin "1") (pinfunction "A_1") (pintype "passive"))
    )
    (net (code "89") (name "/PDPINTA") (class "Default")
      (node (ref "CN3") (pin "15") (pinfunction "15_15") (pintype "passive"))
      (node (ref "P6") (pin "10") (pinfunction "10_10") (pintype "passive"))
    )
    (net (code "90") (name "/PDPINTB") (class "Default")
      (node (ref "CN3") (pin "19") (pinfunction "19_19") (pintype "passive"))
      (node (ref "P5") (pin "10") (pinfunction "10_10") (pintype "passive"))
    )
    (net (code "91") (name "/PWM1") (class "Default")
      (node (ref "CN1") (pin "3") (pinfunction "3_3") (pintype "passive"))
      (node (ref "P6") (pin "17") (pinfunction "17_17") (pintype "passive"))
      (node (ref "RP1") (pin "1") (pinfunction "1_1") (pintype "passive"))
    )
    (net (code "92") (name "/PWM2") (class "Default")
      (node (ref "CN1") (pin "5") (pinfunction "5_5") (pintype "passive"))
      (node (ref "P6") (pin "18") (pinfunction "18_18") (pintype "passive"))
      (node (ref "RP1") (pin "2") (pinfunction "2_2") (pintype "passive"))
    )
    (net (code "93") (name "/PWM3") (class "Default")
      (node (ref "CN1") (pin "7") (pinfunction "7_7") (pintype "passive"))
      (node (ref "P6") (pin "15") (pinfunction "15_15") (pintype "passive"))
      (node (ref "RP1") (pin "3") (pinfunction "3_3") (pintype "passive"))
    )
    (net (code "94") (name "/PWM4") (class "Default")
      (node (ref "CN1") (pin "9") (pinfunction "9_9") (pintype "passive"))
      (node (ref "P6") (pin "16") (pinfunction "16_16") (pintype "passive"))
      (node (ref "RP2") (pin "1") (pinfunction "1_1") (pintype "passive"))
    )
    (net (code "95") (name "/PWM5") (class "Default")
      (node (ref "CN1") (pin "11") (pinfunction "11_11") (pintype "passive"))
      (node (ref "P6") (pin "13") (pinfunction "13_13") (pintype "passive"))
      (node (ref "RP2") (pin "2") (pinfunction "2_2") (pintype "passive"))
    )
    (net (code "96") (name "/PWM6") (class "Default")
      (node (ref "CN1") (pin "13") (pinfunction "13_13") (pintype "passive"))
      (node (ref "P6") (pin "14") (pinfunction "14_14") (pintype "passive"))
      (node (ref "RP2") (pin "3") (pinfunction "3_3") (pintype "passive"))
    )
    (net (code "97") (name "/PWM7") (class "Default")
      (node (ref "CN1") (pin "19") (pinfunction "19_19") (pintype "passive"))
      (node (ref "P5") (pin "17") (pinfunction "17_17") (pintype "passive"))
      (node (ref "RP3") (pin "1") (pinfunction "1_1") (pintype "passive"))
    )
    (net (code "98") (name "/PWM8") (class "Default")
      (node (ref "CN1") (pin "21") (pinfunction "21_21") (pintype "passive"))
      (node (ref "P5") (pin "18") (pinfunction "18_18") (pintype "passive"))
      (node (ref "RP3") (pin "2") (pinfunction "2_2") (pintype "passive"))
    )
    (net (code "99") (name "/PWM9") (class "Default")
      (node (ref "CN1") (pin "23") (pinfunction "23_23") (pintype "passive"))
      (node (ref "P5") (pin "15") (pinfunction "15_15") (pintype "passive"))
      (node (ref "RP3") (pin "3") (pinfunction "3_3") (pintype "passive"))
    )
    (net (code "100") (name "/PWM10") (class "Default")
      (node (ref "CN1") (pin "25") (pinfunction "25_25") (pintype "passive"))
      (node (ref "P5") (pin "16") (pinfunction "16_16") (pintype "passive"))
      (node (ref "RP4") (pin "1") (pinfunction "1_1") (pintype "passive"))
    )
    (net (code "101") (name "/PWM11") (class "Default")
      (node (ref "CN1") (pin "27") (pinfunction "27_27") (pintype "passive"))
      (node (ref "P5") (pin "13") (pinfunction "13_13") (pintype "passive"))
      (node (ref "RP4") (pin "2") (pinfunction "2_2") (pintype "passive"))
    )
    (net (code "102") (name "/PWM12") (class "Default")
      (node (ref "CN1") (pin "29") (pinfunction "29_29") (pintype "passive"))
      (node (ref "P5") (pin "14") (pinfunction "14_14") (pintype "passive"))
      (node (ref "RP4") (pin "3") (pinfunction "3_3") (pintype "passive"))
    )
    (net (code "103") (name "/Q1") (class "Default")
      (node (ref "P3") (pin "6") (pinfunction "6_6") (pintype "passive"))
      (node (ref "R6") (pin "2") (pinfunction "2_2") (pintype "passive"))
      (node (ref "U2") (pin "1") (pinfunction "A_1") (pintype "passive"))
    )
    (net (code "104") (name "/Q2") (class "Default")
      (node (ref "P3") (pin "3") (pinfunction "3_3") (pintype "passive"))
      (node (ref "R9") (pin "2") (pinfunction "2_2") (pintype "passive"))
      (node (ref "U5") (pin "1") (pinfunction "A_1") (pintype "passive"))
    )
    (net (code "105") (name "/R1") (class "Default")
      (node (ref "P3") (pin "5") (pinfunction "5_5") (pintype "passive"))
      (node (ref "R7") (pin "2") (pinfunction "2_2") (pintype "passive"))
      (node (ref "U3") (pin "1") (pinfunction "A_1") (pintype "passive"))
    )
    (net (code "106") (name "/R2") (class "Default")
      (node (ref "P3") (pin "2") (pinfunction "2_2") (pintype "passive"))
      (node (ref "R10") (pin "2") (pinfunction "2_2") (pintype "passive"))
      (node (ref "U6") (pin "1") (pinfunction "A_1") (pintype "passive"))
    )
    (net (code "107") (name "/RELAY1") (class "Default")
      (node (ref "CN3") (pin "6") (pinfunction "6_6") (pintype "passive"))
      (node (ref "P6") (pin "9") (pinfunction "9_9") (pintype "passive"))
    )
    (net (code "108") (name "/RELAY2") (class "Default")
      (node (ref "CN1") (pin "34") (pinfunction "34_34") (pintype "passive"))
      (node (ref "P5") (pin "9") (pinfunction "9_9") (pintype "passive"))
    )
    (net (code "109") (name "/RST1") (class "Default")
      (node (ref "CN1") (pin "15") (pinfunction "15_15") (pintype "passive"))
      (node (ref "P6") (pin "11") (pinfunction "11_11") (pintype "passive"))
    )
    (net (code "110") (name "/RST2") (class "Default")
      (node (ref "CN1") (pin "33") (pinfunction "33_33") (pintype "passive"))
      (node (ref "P5") (pin "12") (pinfunction "12_12") (pintype "passive"))
    )
    (net (code "111") (name "/SPICLKA") (class "Default")
      (node (ref "CN3") (pin "12") (pinfunction "12_12") (pintype "passive+no_connect"))
    )
    (net (code "112") (name "/SPISTEA") (class "Default")
      (node (ref "CN3") (pin "14") (pinfunction "14_14") (pintype "passive+no_connect"))
    )
    (net (code "113") (name "/TXD_A") (class "Default")
      (node (ref "CN3") (pin "4") (pinfunction "4_4") (pintype "passive+no_connect"))
    )
    (net (code "114") (name "/{slash}CS0_1") (class "Default")
      (node (ref "CN2") (pin "39") (pinfunction "39_39") (pintype "passive"))
    )
    (net (code "115") (name "/{slash}CS2") (class "Default")
      (node (ref "CN2") (pin "40") (pinfunction "40_40") (pintype "passive"))
    )
    (net (code "116") (name "/{slash}CS6_7") (class "Default")
      (node (ref "CN2") (pin "41") (pinfunction "41_41") (pintype "passive"))
    )
    (net (code "117") (name "/{slash}RD") (class "Default")
      (node (ref "CN2") (pin "37") (pinfunction "37_37") (pintype "passive"))
    )
    (net (code "118") (name "/{slash}WR") (class "Default")
      (node (ref "CN2") (pin "38") (pinfunction "38_38") (pintype "passive"))
    )
    (net (code "119") (name "3.3_OPT") (class "Default")
      (node (ref "C12") (pin "2") (pinfunction "2_2") (pintype "passive"))
      (node (ref "C16") (pin "2") (pinfunction "2_2") (pintype "passive"))
      (node (ref "C23") (pin "1") (pinfunction "1_1") (pintype "passive"))
      (node (ref "C25") (pin "2") (pinfunction "2_2") (pintype "passive"))
      (node (ref "D11") (pin "2") (pinfunction "K_2") (pintype "passive"))
      (node (ref "D13") (pin "2") (pinfunction "K_2") (pintype "passive"))
      (node (ref "D15") (pin "2") (pinfunction "K_2") (pintype "passive"))
      (node (ref "D17") (pin "2") (pinfunction "K_2") (pintype "passive"))
      (node (ref "D5") (pin "2") (pinfunction "K_2") (pintype "passive"))
      (node (ref "D7") (pin "2") (pinfunction "K_2") (pintype "passive"))
      (node (ref "D9") (pin "2") (pinfunction "K_2") (pintype "passive"))
      (node (ref "R1") (pin "2") (pinfunction "2_2") (pintype "passive"))
      (node (ref "R11") (pin "2") (pinfunction "2_2") (pintype "passive"))
      (node (ref "R12") (pin "2") (pinfunction "2_2") (pintype "passive"))
      (node (ref "R13") (pin "2") (pinfunction "2_2") (pintype "passive"))
      (node (ref "R20") (pin "2") (pinfunction "2_2") (pintype "passive"))
      (node (ref "R22") (pin "2") (pinfunction "2_2") (pintype "passive"))
      (node (ref "R24") (pin "2") (pinfunction "2_2") (pintype "passive"))
      (node (ref "R3") (pin "2") (pinfunction "2_2") (pintype "passive"))
      (node (ref "R4") (pin "2") (pinfunction "2_2") (pintype "passive"))
      (node (ref "RP1") (pin "5") (pinfunction "13_5") (pintype "passive"))
      (node (ref "RP1") (pin "6") (pinfunction "14_6") (pintype "passive"))
      (node (ref "RP1") (pin "7") (pinfunction "15_7") (pintype "passive"))
      (node (ref "RP1") (pin "8") (pinfunction "16_8") (pintype "passive"))
      (node (ref "RP2") (pin "5") (pinfunction "13_5") (pintype "passive"))
      (node (ref "RP2") (pin "6") (pinfunction "14_6") (pintype "passive"))
      (node (ref "RP2") (pin "7") (pinfunction "15_7") (pintype "passive"))
      (node (ref "RP2") (pin "8") (pinfunction "16_8") (pintype "passive"))
      (node (ref "RP3") (pin "5") (pinfunction "13_5") (pintype "passive"))
      (node (ref "RP3") (pin "6") (pinfunction "14_6") (pintype "passive"))
      (node (ref "RP3") (pin "7") (pinfunction "15_7") (pintype "passive"))
      (node (ref "RP3") (pin "8") (pinfunction "16_8") (pintype "passive"))
      (node (ref "RP4") (pin "5") (pinfunction "13_5") (pintype "passive"))
      (node (ref "RP4") (pin "6") (pinfunction "14_6") (pintype "passive"))
      (node (ref "RP4") (pin "7") (pinfunction "15_7") (pintype "passive"))
      (node (ref "RP4") (pin "8") (pinfunction "16_8") (pintype "passive"))
      (node (ref "U1") (pin "6") (pinfunction "C_6") (pintype "passive"))
      (node (ref "U10") (pin "6") (pinfunction "C_6") (pintype "passive"))
      (node (ref "U11") (pin "6") (pinfunction "C_6") (pintype "passive"))
      (node (ref "U12") (pin "6") (pinfunction "C_6") (pintype "passive"))
      (node (ref "U13") (pin "2") (pintype "passive"))
      (node (ref "U13") (pin "4") (pintype "passive"))
      (node (ref "U2") (pin "6") (pinfunction "C_6") (pintype "passive"))
      (node (ref "U3") (pin "6") (pinfunction "C_6") (pintype "passive"))
      (node (ref "U4") (pin "6") (pinfunction "C_6") (pintype "passive"))
      (node (ref "U5") (pin "6") (pinfunction "C_6") (pintype "passive"))
      (node (ref "U6") (pin "6") (pinfunction "C_6") (pintype "passive"))
      (node (ref "U7") (pin "6") (pinfunction "C_6") (pintype "passive"))
      (node (ref "U8") (pin "6") (pinfunction "C_6") (pintype "passive"))
      (node (ref "U9") (pin "6") (pinfunction "C_6") (pintype "passive"))
      (node (ref "UP1") (pin "14") (pinfunction "VCC_14") (pintype "passive"))
      (node (ref "UR1") (pin "14") (pinfunction "VCC_14") (pintype "passive"))
    )
    (net (code "120") (name "A+5V") (class "Default")
      (node (ref "C24") (pin "2") (pinfunction "2_2") (pintype "passive"))
      (node (ref "C28") (pin "2") (pinfunction "2_2") (pintype "passive"))
      (node (ref "C29") (pin "1") (pinfunction "1_1") (pintype "passive"))
      (node (ref "L2") (pin "2") (pinfunction "2_2") (pintype "passive"))
      (node (ref "U13") (pin "3") (pintype "passive"))
    )
    (net (code "121") (name "AGND") (class "Default")
      (node (ref "C13") (pin "1") (pinfunction "1_1") (pintype "passive"))
      (node (ref "C14") (pin "1") (pinfunction "1_1") (pintype "passive"))
      (node (ref "C15") (pin "1") (pinfunction "1_1") (pintype "passive"))
      (node (ref "C28") (pin "1") (pinfunction "1_1") (pintype "passive"))
      (node (ref "C29") (pin "2") (pinfunction "2_2") (pintype "passive"))
      (node (ref "D10") (pin "1") (pinfunction "A_1") (pintype "passive"))
      (node (ref "D12") (pin "1") (pinfunction "A_1") (pintype "passive"))
      (node (ref "D14") (pin "1") (pinfunction "A_1") (pintype "passive"))
      (node (ref "D16") (pin "1") (pinfunction "A_1") (pintype "passive"))
      (node (ref "D18") (pin "1") (pinfunction "A_1") (pintype "passive"))
      (node (ref "D6") (pin "1") (pinfunction "A_1") (pintype "passive"))
      (node (ref "D8") (pin "1") (pinfunction "A_1") (pintype "passive"))
      (node (ref "L3") (pin "1") (pinfunction "1_1") (pintype "passive"))
      (node (ref "L4") (pin "1") (pinfunction "1_1") (pintype "passive"))
      (node (ref "P4") (pin "3") (pinfunction "3_3") (pintype "passive"))
      (node (ref "P5") (pin "5") (pinfunction "5_5") (pintype "passive"))
      (node (ref "P5") (pin "6") (pinfunction "6_6") (pintype "passive"))
      (node (ref "P6") (pin "5") (pinfunction "5_5") (pintype "passive"))
      (node (ref "R21") (pin "1") (pinfunction "TOP_1") (pintype "passive"))
      (node (ref "R23") (pin "1") (pinfunction "TOP_1") (pintype "passive"))
      (node (ref "T7") (pin "1") (pinfunction "A_1") (pintype "passive"))
    )
    (net (code "122") (name "GND") (class "Default")
      (node (ref "C10") (pin "1") (pinfunction "1_1") (pintype "passive"))
      (node (ref "C11") (pin "1") (pinfunction "1_1") (pintype "passive"))
      (node (ref "C12") (pin "1") (pinfunction "1_1") (pintype "passive"))
      (node (ref "C16") (pin "1") (pinfunction "1_1") (pintype "passive"))
      (node (ref "C17") (pin "1") (pinfunction "1_1") (pintype "passive"))
      (node (ref "C18") (pin "1") (pinfunction "1_1") (pintype "passive"))
      (node (ref "C19") (pin "1") (pinfunction "1_1") (pintype "passive"))
      (node (ref "C20") (pin "1") (pinfunction "1_1") (pintype "passive"))
      (node (ref "C21") (pin "1") (pinfunction "1_1") (pintype "passive"))
      (node (ref "C22") (pin "1") (pinfunction "1_1") (pintype "passive"))
      (node (ref "C23") (pin "2") (pinfunction "2_2") (pintype "passive"))
      (node (ref "C24") (pin "1") (pinfunction "1_1") (pintype "passive"))
      (node (ref "C25") (pin "1") (pinfunction "1_1") (pintype "passive"))
      (node (ref "C26") (pin "1") (pinfunction "1_1") (pintype "passive"))
      (node (ref "C27") (pin "2") (pinfunction "2_2") (pintype "passive"))
      (node (ref "C3") (pin "1") (pinfunction "1_1") (pintype "passive"))
      (node (ref "C4") (pin "1") (pinfunction "1_1") (pintype "passive"))
      (node (ref "C5") (pin "1") (pinfunction "1_1") (pintype "passive"))
      (node (ref "C6") (pin "1") (pinfunction "1_1") (pintype "passive"))
      (node (ref "C7") (pin "1") (pinfunction "1_1") (pintype "passive"))
      (node (ref "C8") (pin "1") (pinfunction "1_1") (pintype "passive"))
      (node (ref "C9") (pin "1") (pinfunction "1_1") (pintype "passive"))
      (node (ref "CN1") (pin "35") (pinfunction "35_35") (pintype "passive"))
      (node (ref "CN1") (pin "36") (pinfunction "36_36") (pintype "passive"))
      (node (ref "CN1") (pin "49") (pinfunction "49_49") (pintype "passive"))
      (node (ref "CN1") (pin "50") (pinfunction "50_50") (pintype "passive"))
      (node (ref "CN2") (pin "49") (pinfunction "49_49") (pintype "passive"))
      (node (ref "CN2") (pin "50") (pinfunction "50_50") (pintype "passive"))
      (node (ref "CN3") (pin "29") (pinfunction "29_29") (pintype "passive"))
      (node (ref "CN3") (pin "30") (pinfunction "30_30") (pintype "passive"))
      (node (ref "L3") (pin "2") (pinfunction "2_2") (pintype "passive"))
      (node (ref "L4") (pin "2") (pinfunction "2_2") (pintype "passive"))
      (node (ref "P5") (pin "7") (pinfunction "7_7") (pintype "passive"))
      (node (ref "P5") (pin "8") (pinfunction "8_8") (pintype "passive"))
      (node (ref "P6") (pin "7") (pinfunction "7_7") (pintype "passive"))
      (node (ref "P6") (pin "8") (pinfunction "8_8") (pintype "passive"))
      (node (ref "Q1") (pin "2") (pinfunction "E_2") (pintype "passive"))
      (node (ref "R14") (pin "2") (pinfunction "2_2") (pintype "passive"))
      (node (ref "R15") (pin "2") (pinfunction "2_2") (pintype "passive"))
      (node (ref "R16") (pin "2") (pinfunction "2_2") (pintype "passive"))
      (node (ref "R17") (pin "2") (pinfunction "2_2") (pintype "passive"))
      (node (ref "R18") (pin "2") (pinfunction "2_2") (pintype "passive"))
      (node (ref "R19") (pin "2") (pinfunction "2_2") (pintype "passive"))
      (node (ref "R31") (pin "2") (pinfunction "2_2") (pintype "passive"))
      (node (ref "R32") (pin "2") (pinfunction "2_2") (pintype "passive"))
      (node (ref "R33") (pin "2") (pinfunction "2_2") (pintype "passive"))
      (node (ref "R34") (pin "2") (pinfunction "2_2") (pintype "passive"))
      (node (ref "R35") (pin "2") (pinfunction "2_2") (pintype "passive"))
      (node (ref "R36") (pin "2") (pinfunction "2_2") (pintype "passive"))
      (node (ref "R37") (pin "2") (pinfunction "2_2") (pintype "passive"))
      (node (ref "T8") (pin "1") (pinfunction "A_1") (pintype "passive"))
      (node (ref "U13") (pin "1") (pintype "passive"))
      (node (ref "UP1") (pin "7") (pinfunction "GND_7") (pintype "passive"))
      (node (ref "UR1") (pin "7") (pinfunction "GND_7") (pintype "passive"))
      (node (ref "key1") (pin "1") (pinfunction "1_1") (pintype "passive"))
      (node (ref "key2") (pin "1") (pinfunction "1_1") (pintype "passive"))
      (node (ref "key3") (pin "1") (pinfunction "1_1") (pintype "passive"))
    )
    (net (code "123") (name "GND_HALL") (class "Default")
      (node (ref "C1") (pin "1") (pinfunction "1_1") (pintype "passive"))
      (node (ref "C2") (pin "2") (pinfunction "2_2") (pintype "passive"))
      (node (ref "P1") (pin "1") (pinfunction "1_1") (pintype "passive"))
      (node (ref "P2") (pin "1") (pinfunction "1_1") (pintype "passive"))
      (node (ref "P3") (pin "1") (pinfunction "1_1") (pintype "passive"))
      (node (ref "R2") (pin "1") (pinfunction "1_1") (pintype "passive"))
      (node (ref "U1") (pin "3") (pinfunction "K_3") (pintype "passive"))
      (node (ref "U10") (pin "3") (pinfunction "K_3") (pintype "passive"))
      (node (ref "U11") (pin "3") (pinfunction "K_3") (pintype "passive"))
      (node (ref "U12") (pin "3") (pinfunction "K_3") (pintype "passive"))
      (node (ref "U2") (pin "3") (pinfunction "K_3") (pintype "passive"))
      (node (ref "U3") (pin "3") (pinfunction "K_3") (pintype "passive"))
      (node (ref "U4") (pin "3") (pinfunction "K_3") (pintype "passive"))
      (node (ref "U5") (pin "3") (pinfunction "K_3") (pintype "passive"))
      (node (ref "U6") (pin "3") (pinfunction "K_3") (pintype "passive"))
      (node (ref "U7") (pin "3") (pinfunction "K_3") (pintype "passive"))
      (node (ref "U8") (pin "3") (pinfunction "K_3") (pintype "passive"))
      (node (ref "U9") (pin "3") (pinfunction "K_3") (pintype "passive"))
    )
    (net (code "124") (name "Net-(Buzzer1--)") (class "Default")
      (node (ref "Buzzer1") (pin "2") (pinfunction "-_2") (pintype "passive"))
      (node (ref "D19") (pin "1") (pinfunction "A_1") (pintype "passive"))
      (node (ref "Q1") (pin "3") (pinfunction "C_3") (pintype "passive"))
    )
    (net (code "125") (name "Net-(D1-A)") (class "Default")
      (node (ref "D1") (pin "1") (pinfunction "A_1") (pintype "passive"))
      (node (ref "R1") (pin "1") (pinfunction "1_1") (pintype "passive"))
    )
    (net (code "126") (name "Net-(D2-K)") (class "Default")
      (node (ref "D2") (pin "2") (pinfunction "K_2") (pintype "passive"))
      (node (ref "R2") (pin "2") (pinfunction "2_2") (pintype "passive"))
    )
    (net (code "127") (name "Net-(D3-A)") (class "Default")
      (node (ref "D3") (pin "1") (pinfunction "A_1") (pintype "passive"))
      (node (ref "R3") (pin "1") (pinfunction "1_1") (pintype "passive"))
    )
    (net (code "128") (name "Net-(D4-A)") (class "Default")
      (node (ref "D4") (pin "1") (pinfunction "A_1") (pintype "passive"))
      (node (ref "R4") (pin "1") (pinfunction "1_1") (pintype "passive"))
    )
    (net (code "129") (name "Net-(P4-Pad1)") (class "Default")
      (node (ref "P4") (pin "1") (pinfunction "1_1") (pintype "passive"))
      (node (ref "R24") (pin "1") (pinfunction "1_1") (pintype "passive"))
    )
    (net (code "130") (name "Net-(Q1-B)") (class "Default")
      (node (ref "Q1") (pin "1") (pinfunction "B_1") (pintype "passive"))
      (node (ref "R38") (pin "1") (pinfunction "1_1") (pintype "passive"))
    )
    (net (code "131") (name "Net-(R21-BOT)") (class "Default")
      (node (ref "R20") (pin "1") (pinfunction "1_1") (pintype "passive"))
      (node (ref "R21") (pin "3") (pinfunction "BOT_3") (pintype "passive"))
    )
    (net (code "132") (name "Net-(R23-BOT)") (class "Default")
      (node (ref "R22") (pin "1") (pinfunction "1_1") (pintype "passive"))
      (node (ref "R23") (pin "3") (pinfunction "BOT_3") (pintype "passive"))
    )
    (net (code "133") (name "Net-(U1-E)") (class "Default")
      (node (ref "C6") (pin "2") (pinfunction "2_2") (pintype "passive"))
      (node (ref "R14") (pin "1") (pinfunction "1_1") (pintype "passive"))
      (node (ref "U1") (pin "4") (pinfunction "E_4") (pintype "passive"))
      (node (ref "UR1") (pin "1") (pinfunction "A_1") (pintype "input"))
    )
    (net (code "134") (name "Net-(U2-E)") (class "Default")
      (node (ref "C7") (pin "2") (pinfunction "2_2") (pintype "passive"))
      (node (ref "R15") (pin "1") (pinfunction "1_1") (pintype "passive"))
      (node (ref "U2") (pin "4") (pinfunction "E_4") (pintype "passive"))
      (node (ref "UR1") (pin "3") (pinfunction "A_3") (pintype "input"))
    )
    (net (code "135") (name "Net-(U3-E)") (class "Default")
      (node (ref "C8") (pin "2") (pinfunction "2_2") (pintype "passive"))
      (node (ref "R16") (pin "1") (pinfunction "1_1") (pintype "passive"))
      (node (ref "U3") (pin "4") (pinfunction "E_4") (pintype "passive"))
      (node (ref "UR1") (pin "5") (pinfunction "A_5") (pintype "input"))
    )
    (net (code "136") (name "Net-(U4-E)") (class "Default")
      (node (ref "C9") (pin "2") (pinfunction "2_2") (pintype "passive"))
      (node (ref "R17") (pin "1") (pinfunction "1_1") (pintype "passive"))
      (node (ref "U4") (pin "4") (pinfunction "E_4") (pintype "passive"))
      (node (ref "UR1") (pin "9") (pinfunction "A_9") (pintype "input"))
    )
    (net (code "137") (name "Net-(U5-E)") (class "Default")
      (node (ref "C10") (pin "2") (pinfunction "2_2") (pintype "passive"))
      (node (ref "R18") (pin "1") (pinfunction "1_1") (pintype "passive"))
      (node (ref "U5") (pin "4") (pinfunction "E_4") (pintype "passive"))
      (node (ref "UR1") (pin "13") (pinfunction "A_13") (pintype "input"))
    )
    (net (code "138") (name "Net-(U6-E)") (class "Default")
      (node (ref "C11") (pin "2") (pinfunction "2_2") (pintype "passive"))
      (node (ref "R19") (pin "1") (pinfunction "1_1") (pintype "passive"))
      (node (ref "U6") (pin "4") (pinfunction "E_4") (pintype "passive"))
      (node (ref "UR1") (pin "11") (pinfunction "A_11") (pintype "input"))
    )
    (net (code "139") (name "Net-(U7-E)") (class "Default")
      (node (ref "C17") (pin "2") (pinfunction "2_2") (pintype "passive"))
      (node (ref "R31") (pin "1") (pinfunction "1_1") (pintype "passive"))
      (node (ref "U7") (pin "4") (pinfunction "E_4") (pintype "passive"))
      (node (ref "UP1") (pin "1") (pinfunction "A_1") (pintype "input"))
    )
    (net (code "140") (name "Net-(U8-E)") (class "Default")
      (node (ref "C18") (pin "2") (pinfunction "2_2") (pintype "passive"))
      (node (ref "R32") (pin "1") (pinfunction "1_1") (pintype "passive"))
      (node (ref "U8") (pin "4") (pinfunction "E_4") (pintype "passive"))
      (node (ref "UP1") (pin "3") (pinfunction "A_3") (pintype "input"))
    )
    (net (code "141") (name "Net-(U9-E)") (class "Default")
      (node (ref "C19") (pin "2") (pinfunction "2_2") (pintype "passive"))
      (node (ref "R33") (pin "1") (pinfunction "1_1") (pintype "passive"))
      (node (ref "U9") (pin "4") (pinfunction "E_4") (pintype "passive"))
      (node (ref "UP1") (pin "5") (pinfunction "A_5") (pintype "input"))
    )
    (net (code "142") (name "Net-(U10-E)") (class "Default")
      (node (ref "C20") (pin "2") (pinfunction "2_2") (pintype "passive"))
      (node (ref "R34") (pin "1") (pinfunction "1_1") (pintype "passive"))
      (node (ref "U10") (pin "4") (pinfunction "E_4") (pintype "passive"))
      (node (ref "UP1") (pin "9") (pinfunction "A_9") (pintype "input"))
    )
    (net (code "143") (name "Net-(U11-E)") (class "Default")
      (node (ref "C21") (pin "2") (pinfunction "2_2") (pintype "passive"))
      (node (ref "R35") (pin "1") (pinfunction "1_1") (pintype "passive"))
      (node (ref "U11") (pin "4") (pinfunction "E_4") (pintype "passive"))
      (node (ref "UP1") (pin "13") (pinfunction "A_13") (pintype "input"))
    )
    (net (code "144") (name "Net-(U12-E)") (class "Default")
      (node (ref "C22") (pin "2") (pinfunction "2_2") (pintype "passive"))
      (node (ref "R36") (pin "1") (pinfunction "1_1") (pintype "passive"))
      (node (ref "U12") (pin "4") (pinfunction "E_4") (pintype "passive"))
      (node (ref "UP1") (pin "11") (pinfunction "A_11") (pintype "input"))
    )
    (net (code "145") (name "unconnected-(CN2-Pad43)") (class "Default")
      (node (ref "CN2") (pin "43") (pinfunction "43_43") (pintype "passive"))
    )
    (net (code "146") (name "unconnected-(CN2-Pad44)") (class "Default")
      (node (ref "CN2") (pin "44") (pinfunction "44_44") (pintype "passive"))
    )
    (net (code "147") (name "unconnected-(CN2-Pad45)") (class "Default")
      (node (ref "CN2") (pin "45") (pinfunction "45_45") (pintype "passive+no_connect"))
    )
    (net (code "148") (name "unconnected-(CN2-Pad46)") (class "Default")
      (node (ref "CN2") (pin "46") (pinfunction "46_46") (pintype "passive+no_connect"))
    )
    (net (code "149") (name "unconnected-(CN2-Pad47)") (class "Default")
      (node (ref "CN2") (pin "47") (pinfunction "47_47") (pintype "passive+no_connect"))
    )
    (net (code "150") (name "unconnected-(CN2-Pad48)") (class "Default")
      (node (ref "CN2") (pin "48") (pinfunction "48_48") (pintype "passive+no_connect"))
    )
    (net (code "151") (name "unconnected-(P5-Pad3)") (class "Default")
      (node (ref "P5") (pin "3") (pinfunction "3_3") (pintype "passive+no_connect"))
    )
    (net (code "152") (name "unconnected-(RP1-Pad4)") (class "Default")
      (node (ref "RP1") (pin "4") (pinfunction "4_4") (pintype "passive+no_connect"))
    )
    (net (code "153") (name "unconnected-(RP2-Pad4)") (class "Default")
      (node (ref "RP2") (pin "4") (pinfunction "4_4") (pintype "passive+no_connect"))
    )
    (net (code "154") (name "unconnected-(RP3-Pad4)") (class "Default")
      (node (ref "RP3") (pin "4") (pinfunction "4_4") (pintype "passive+no_connect"))
    )
    (net (code "155") (name "unconnected-(RP4-Pad4)") (class "Default")
      (node (ref "RP4") (pin "4") (pinfunction "4_4") (pintype "passive+no_connect"))
    )
  )
)
